# ece411-t04-filamint-V4_6.net
KiCad netlist of a schematic drawn in EAGLE
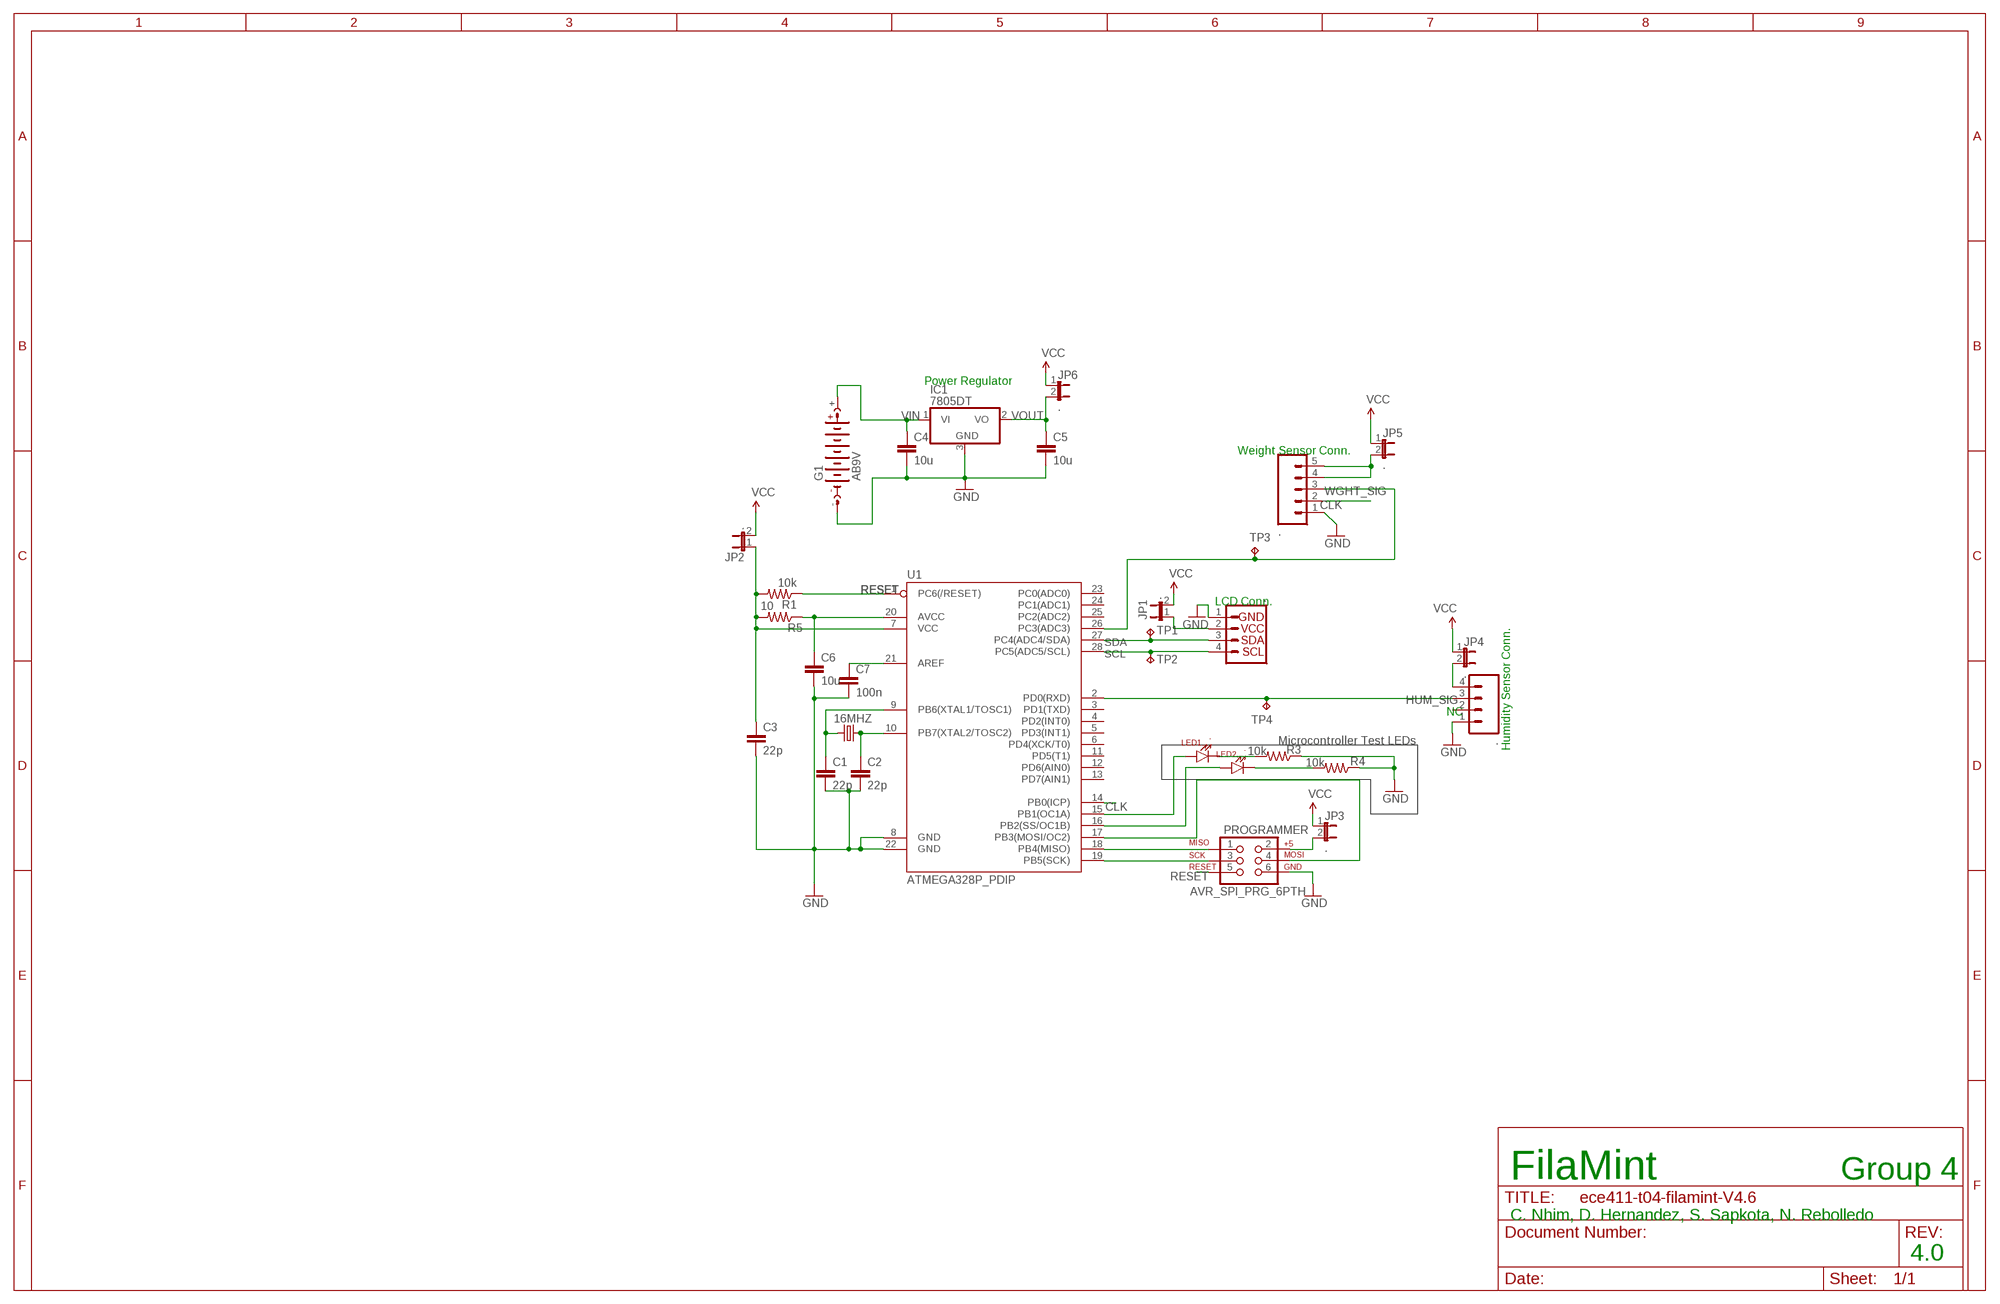
[diagram p0: schematic, sheet 1]

(export (version "E")
  (design (tool "Eeschema 10.0.6"))
  (components
    (comp (ref "16MHZ")
      (value "CSM-7X-DU")
      (footprint "eagle-import:CSM-7X-DU")
      (libsource (lib "eagle-import") (part "CSM-7X-DU"))
    )
    (comp (ref "C1")
      (value "22p")
      (footprint "eagle-import:C025-024X044")
      (libsource (lib "eagle-import") (part "C-EU025-024X044"))
    )
    (comp (ref "C2")
      (value "22p")
      (footprint "eagle-import:C025-024X044")
      (libsource (lib "eagle-import") (part "C-EU025-024X044"))
    )
    (comp (ref "C3")
      (value "22p")
      (footprint "eagle-import:C025-024X044")
      (libsource (lib "eagle-import") (part "C-EU025-024X044"))
    )
    (comp (ref "C4")
      (value "10u")
      (footprint "eagle-import:C025-024X044")
      (libsource (lib "eagle-import") (part "C-EU025-024X044"))
    )
    (comp (ref "C5")
      (value "10u")
      (footprint "eagle-import:C025-024X044")
      (libsource (lib "eagle-import") (part "C-EU025-024X044"))
    )
    (comp (ref "C6")
      (value "10u")
      (footprint "eagle-import:C025-024X044")
      (libsource (lib "eagle-import") (part "C-EU025-024X044"))
    )
    (comp (ref "C7")
      (value "100n")
      (footprint "eagle-import:C025-024X044")
      (libsource (lib "eagle-import") (part "C-EU025-024X044"))
    )
    (comp (ref "DHT22")
      (value ".")
      (footprint "eagle-import:1X04-1MM-RA")
      (libsource (lib "eagle-import") (part "M04SMD2"))
    )
    (comp (ref "G1")
      (value "AB9V")
      (footprint "eagle-import:AB9V")
      (libsource (lib "eagle-import") (part "AB9V"))
    )
    (comp (ref "HX711")
      (value ".")
      (footprint "eagle-import:1X05-1MM")
      (libsource (lib "eagle-import") (part "M05SMD"))
    )
    (comp (ref "IC1")
      (value "7805DT")
      (footprint "eagle-import:TO252")
      (libsource (lib "eagle-import") (part "78DT05"))
    )
    (comp (ref "JP1")
      (value ".")
      (footprint "eagle-import:JP1")
      (libsource (lib "eagle-import") (part "JP1E"))
    )
    (comp (ref "JP2")
      (value ".")
      (footprint "eagle-import:JP1")
      (libsource (lib "eagle-import") (part "JP1E"))
    )
    (comp (ref "JP3")
      (value ".")
      (footprint "eagle-import:JP1")
      (libsource (lib "eagle-import") (part "JP1E"))
    )
    (comp (ref "JP4")
      (value ".")
      (footprint "eagle-import:JP1")
      (libsource (lib "eagle-import") (part "JP1E"))
    )
    (comp (ref "JP5")
      (value ".")
      (footprint "eagle-import:JP1")
      (libsource (lib "eagle-import") (part "JP1E"))
    )
    (comp (ref "JP6")
      (value ".")
      (footprint "eagle-import:JP1")
      (libsource (lib "eagle-import") (part "JP1E"))
    )
    (comp (ref "LCD")
      (value ".")
      (footprint "eagle-import:1X04")
      (libsource (lib "eagle-import") (part "I2C_STANDARD"))
    )
    (comp (ref "LED1")
      (value ".")
      (footprint "eagle-import:LTE-302")
      (libsource (lib "eagle-import") (part "LTE-302"))
    )
    (comp (ref "LED2")
      (value ".")
      (footprint "eagle-import:LTE-302")
      (libsource (lib "eagle-import") (part "LTE-302"))
    )
    (comp (ref "PROGRAMMER")
      (value "AVR_SPI_PRG_6PTH")
      (footprint "eagle-import:2X3")
      (libsource (lib "eagle-import") (part "AVR_SPI_PRG_6PTH"))
    )
    (comp (ref "R1")
      (value "10k")
      (footprint "eagle-import:0204_5")
      (libsource (lib "eagle-import") (part "R-US_0204/5"))
    )
    (comp (ref "R3")
      (value "10k")
      (footprint "eagle-import:0204_5")
      (libsource (lib "eagle-import") (part "R-US_0204/5"))
    )
    (comp (ref "R4")
      (value "10k")
      (footprint "eagle-import:0204_5")
      (libsource (lib "eagle-import") (part "R-US_0204/5"))
    )
    (comp (ref "R5")
      (value "10")
      (footprint "eagle-import:0204_5")
      (libsource (lib "eagle-import") (part "R-US_0204/5"))
    )
    (comp (ref "TP1")
      (value "TPB1,27")
      (footprint "eagle-import:B1,27")
      (libsource (lib "eagle-import") (part "TPB1,27"))
    )
    (comp (ref "TP2")
      (value "TPB1,27")
      (footprint "eagle-import:B1,27")
      (libsource (lib "eagle-import") (part "TPB1,27"))
    )
    (comp (ref "TP3")
      (value "TPB1,27")
      (footprint "eagle-import:B1,27")
      (libsource (lib "eagle-import") (part "TPB1,27"))
    )
    (comp (ref "TP4")
      (value "TPB1,27")
      (footprint "eagle-import:B1,27")
      (libsource (lib "eagle-import") (part "TPB1,27"))
    )
    (comp (ref "U1")
      (value "ATMEGA328P_PDIP")
      (footprint "eagle-import:DIL28-3")
      (libsource (lib "eagle-import") (part "ATMEGA328P_PDIP"))
    )
  )
  (nets
    (net (code "1") (name "/CLK") (class "Default")
      (node (ref "HX711") (pin "2") (pinfunction "2_2") (pintype "passive"))
      (node (ref "U1") (pin "14") (pinfunction "PB0(ICP)_14") (pintype "bidirectional"))
    )
    (net (code "2") (name "/HUM_SIG") (class "Default")
      (node (ref "DHT22") (pin "3") (pinfunction "3_3") (pintype "passive"))
      (node (ref "TP4") (pin "TP") (pinfunction "TP_TP") (pintype "input"))
      (node (ref "U1") (pin "2") (pinfunction "PD0(RXD)_2") (pintype "bidirectional"))
    )
    (net (code "3") (name "/RESET") (class "Default")
      (node (ref "PROGRAMMER") (pin "5") (pinfunction "5_5") (pintype "passive"))
      (node (ref "R1") (pin "1") (pinfunction "1_1") (pintype "passive"))
      (node (ref "U1") (pin "1") (pinfunction "PC6(/RESET)_1") (pintype "bidirectional"))
    )
    (net (code "4") (name "/SCL") (class "Default")
      (node (ref "LCD") (pin "4") (pinfunction "4_4") (pintype "passive"))
      (node (ref "TP2") (pin "TP") (pinfunction "TP_TP") (pintype "input"))
      (node (ref "U1") (pin "28") (pinfunction "PC5(ADC5/SCL)_28") (pintype "bidirectional"))
    )
    (net (code "5") (name "/SDA") (class "Default")
      (node (ref "LCD") (pin "3") (pinfunction "3_3") (pintype "passive"))
      (node (ref "TP1") (pin "TP") (pinfunction "TP_TP") (pintype "input"))
      (node (ref "U1") (pin "27") (pinfunction "PC4(ADC4/SDA)_27") (pintype "bidirectional"))
    )
    (net (code "6") (name "/VIN") (class "Default")
      (node (ref "C4") (pin "1") (pinfunction "1_1") (pintype "passive"))
      (node (ref "G1") (pin "+") (pinfunction "+_+") (pintype "passive"))
      (node (ref "IC1") (pin "1") (pinfunction "VI_1") (pintype "input"))
    )
    (net (code "7") (name "/WGHT_SIG") (class "Default")
      (node (ref "HX711") (pin "3") (pinfunction "3_3") (pintype "passive"))
      (node (ref "TP3") (pin "TP") (pinfunction "TP_TP") (pintype "input"))
      (node (ref "U1") (pin "26") (pinfunction "PC3(ADC3)_26") (pintype "bidirectional"))
    )
    (net (code "8") (name "GND") (class "Default")
      (node (ref "C1") (pin "2") (pinfunction "2_2") (pintype "passive"))
      (node (ref "C2") (pin "2") (pinfunction "2_2") (pintype "passive"))
      (node (ref "C3") (pin "2") (pinfunction "2_2") (pintype "passive"))
      (node (ref "C4") (pin "2") (pinfunction "2_2") (pintype "passive"))
      (node (ref "C5") (pin "2") (pinfunction "2_2") (pintype "passive"))
      (node (ref "C6") (pin "2") (pinfunction "2_2") (pintype "passive"))
      (node (ref "C7") (pin "2") (pinfunction "2_2") (pintype "passive"))
      (node (ref "DHT22") (pin "1") (pinfunction "1_1") (pintype "passive"))
      (node (ref "G1") (pin "-") (pinfunction "-_-") (pintype "passive"))
      (node (ref "HX711") (pin "1") (pinfunction "1_1") (pintype "passive"))
      (node (ref "IC1") (pin "3") (pinfunction "GND_3") (pintype "passive"))
      (node (ref "LCD") (pin "1") (pinfunction "1_1") (pintype "passive"))
      (node (ref "PROGRAMMER") (pin "6") (pinfunction "6_6") (pintype "passive"))
      (node (ref "R3") (pin "1") (pinfunction "1_1") (pintype "passive"))
      (node (ref "R4") (pin "1") (pinfunction "1_1") (pintype "passive"))
      (node (ref "U1") (pin "22") (pinfunction "GND_22") (pintype "bidirectional"))
      (node (ref "U1") (pin "8") (pinfunction "GND_8") (pintype "bidirectional"))
    )
    (net (code "9") (name "Net-(DHT22-Pad4)") (class "Default")
      (node (ref "DHT22") (pin "4") (pinfunction "4_4") (pintype "passive"))
      (node (ref "JP4") (pin "2") (pinfunction "2_2") (pintype "passive"))
    )
    (net (code "10") (name "Net-(HX711-Pad4)") (class "Default")
      (node (ref "HX711") (pin "4") (pinfunction "4_4") (pintype "passive"))
      (node (ref "HX711") (pin "5") (pinfunction "5_5") (pintype "passive"))
      (node (ref "JP5") (pin "2") (pinfunction "2_2") (pintype "passive"))
    )
    (net (code "11") (name "Net-(IC1-VO)") (class "Default")
      (node (ref "C5") (pin "1") (pinfunction "1_1") (pintype "passive"))
      (node (ref "IC1") (pin "2") (pinfunction "VO_2") (pintype "passive"))
      (node (ref "JP6") (pin "2") (pinfunction "2_2") (pintype "passive"))
    )
    (net (code "12") (name "Net-(JP1-Pad1)") (class "Default")
      (node (ref "JP1") (pin "1") (pinfunction "1_1") (pintype "passive"))
      (node (ref "LCD") (pin "2") (pinfunction "2_2") (pintype "passive"))
    )
    (net (code "13") (name "Net-(JP3-Pad2)") (class "Default")
      (node (ref "JP3") (pin "2") (pinfunction "2_2") (pintype "passive"))
      (node (ref "PROGRAMMER") (pin "2") (pinfunction "2_2") (pintype "passive"))
    )
    (net (code "14") (name "Net-(LED1-PadC)") (class "Default")
      (node (ref "LED1") (pin "C") (pinfunction "C_C") (pintype "bidirectional"))
      (node (ref "R3") (pin "2") (pinfunction "2_2") (pintype "passive"))
    )
    (net (code "15") (name "Net-(LED2-PadC)") (class "Default")
      (node (ref "LED2") (pin "C") (pinfunction "C_C") (pintype "bidirectional"))
      (node (ref "R4") (pin "2") (pinfunction "2_2") (pintype "passive"))
    )
    (net (code "16") (name "Net-(U1-AREF)") (class "Default")
      (node (ref "C7") (pin "1") (pinfunction "1_1") (pintype "passive"))
      (node (ref "U1") (pin "21") (pinfunction "AREF_21") (pintype "bidirectional"))
    )
    (net (code "17") (name "Net-(U1-AVCC)") (class "Default")
      (node (ref "C6") (pin "1") (pinfunction "1_1") (pintype "passive"))
      (node (ref "R5") (pin "1") (pinfunction "1_1") (pintype "passive"))
      (node (ref "U1") (pin "20") (pinfunction "AVCC_20") (pintype "bidirectional"))
    )
    (net (code "18") (name "Net-(U1-PB1(OC1A))") (class "Default")
      (node (ref "LED1") (pin "A") (pinfunction "A_A") (pintype "bidirectional"))
      (node (ref "U1") (pin "15") (pinfunction "PB1(OC1A)_15") (pintype "bidirectional"))
    )
    (net (code "19") (name "Net-(U1-PB2(SS{slash}OC1B))") (class "Default")
      (node (ref "LED2") (pin "A") (pinfunction "A_A") (pintype "bidirectional"))
      (node (ref "U1") (pin "16") (pinfunction "PB2(SS/OC1B)_16") (pintype "bidirectional"))
    )
    (net (code "20") (name "Net-(U1-PB3(MOSI{slash}OC2))") (class "Default")
      (node (ref "PROGRAMMER") (pin "4") (pinfunction "4_4") (pintype "passive"))
      (node (ref "U1") (pin "17") (pinfunction "PB3(MOSI/OC2)_17") (pintype "bidirectional"))
    )
    (net (code "21") (name "Net-(U1-PB4(MISO))") (class "Default")
      (node (ref "PROGRAMMER") (pin "1") (pinfunction "1_1") (pintype "passive"))
      (node (ref "U1") (pin "18") (pinfunction "PB4(MISO)_18") (pintype "bidirectional"))
    )
    (net (code "22") (name "Net-(U1-PB5(SCK))") (class "Default")
      (node (ref "PROGRAMMER") (pin "3") (pinfunction "3_3") (pintype "passive"))
      (node (ref "U1") (pin "19") (pinfunction "PB5(SCK)_19") (pintype "bidirectional"))
    )
    (net (code "23") (name "Net-(U1-PB6(XTAL1{slash}TOSC1))") (class "Default")
      (node (ref "16MHZ") (pin "2") (pinfunction "2_2") (pintype "passive"))
      (node (ref "C1") (pin "1") (pinfunction "1_1") (pintype "passive"))
      (node (ref "U1") (pin "9") (pinfunction "PB6(XTAL1/TOSC1)_9") (pintype "bidirectional"))
    )
    (net (code "24") (name "Net-(U1-PB7(XTAL2{slash}TOSC2))") (class "Default")
      (node (ref "16MHZ") (pin "1") (pinfunction "1_1") (pintype "passive"))
      (node (ref "C2") (pin "1") (pinfunction "1_1") (pintype "passive"))
      (node (ref "U1") (pin "10") (pinfunction "PB7(XTAL2/TOSC2)_10") (pintype "bidirectional"))
    )
    (net (code "25") (name "Net-(U1-VCC)") (class "Default")
      (node (ref "C3") (pin "1") (pinfunction "1_1") (pintype "passive"))
      (node (ref "JP2") (pin "1") (pinfunction "1_1") (pintype "passive"))
      (node (ref "R1") (pin "2") (pinfunction "2_2") (pintype "passive"))
      (node (ref "R5") (pin "2") (pinfunction "2_2") (pintype "passive"))
      (node (ref "U1") (pin "7") (pinfunction "VCC_7") (pintype "bidirectional"))
    )
    (net (code "26") (name "VCC") (class "Default")
      (node (ref "JP1") (pin "2") (pinfunction "2_2") (pintype "passive"))
      (node (ref "JP2") (pin "2") (pinfunction "2_2") (pintype "passive"))
      (node (ref "JP3") (pin "1") (pinfunction "1_1") (pintype "passive"))
      (node (ref "JP4") (pin "1") (pinfunction "1_1") (pintype "passive"))
      (node (ref "JP5") (pin "1") (pinfunction "1_1") (pintype "passive"))
      (node (ref "JP6") (pin "1") (pinfunction "1_1") (pintype "passive"))
    )
    (net (code "27") (name "unconnected-(DHT22-Pad2)") (class "Default")
      (node (ref "DHT22") (pin "2") (pinfunction "2_2") (pintype "passive"))
    )
    (net (code "28") (name "unconnected-(U1-PC0(ADC0)-Pad23)") (class "Default")
      (node (ref "U1") (pin "23") (pinfunction "PC0(ADC0)_23") (pintype "bidirectional"))
    )
    (net (code "29") (name "unconnected-(U1-PC1(ADC1)-Pad24)") (class "Default")
      (node (ref "U1") (pin "24") (pinfunction "PC1(ADC1)_24") (pintype "bidirectional"))
    )
    (net (code "30") (name "unconnected-(U1-PC2(ADC2)-Pad25)") (class "Default")
      (node (ref "U1") (pin "25") (pinfunction "PC2(ADC2)_25") (pintype "bidirectional"))
    )
    (net (code "31") (name "unconnected-(U1-PD1(TXD)-Pad3)") (class "Default")
      (node (ref "U1") (pin "3") (pinfunction "PD1(TXD)_3") (pintype "bidirectional"))
    )
    (net (code "32") (name "unconnected-(U1-PD2(INT0)-Pad4)") (class "Default")
      (node (ref "U1") (pin "4") (pinfunction "PD2(INT0)_4") (pintype "bidirectional"))
    )
    (net (code "33") (name "unconnected-(U1-PD3(INT1)-Pad5)") (class "Default")
      (node (ref "U1") (pin "5") (pinfunction "PD3(INT1)_5") (pintype "bidirectional"))
    )
    (net (code "34") (name "unconnected-(U1-PD4(XCK{slash}T0)-Pad6)") (class "Default")
      (node (ref "U1") (pin "6") (pinfunction "PD4(XCK/T0)_6") (pintype "bidirectional"))
    )
    (net (code "35") (name "unconnected-(U1-PD5(T1)-Pad11)") (class "Default")
      (node (ref "U1") (pin "11") (pinfunction "PD5(T1)_11") (pintype "bidirectional"))
    )
    (net (code "36") (name "unconnected-(U1-PD6(AIN0)-Pad12)") (class "Default")
      (node (ref "U1") (pin "12") (pinfunction "PD6(AIN0)_12") (pintype "bidirectional"))
    )
    (net (code "37") (name "unconnected-(U1-PD7(AIN1)-Pad13)") (class "Default")
      (node (ref "U1") (pin "13") (pinfunction "PD7(AIN1)_13") (pintype "bidirectional"))
    )
  )
)
